# AJH_as3320_HPF_03_4hp.net
KiCad netlist of a schematic drawn in EAGLE
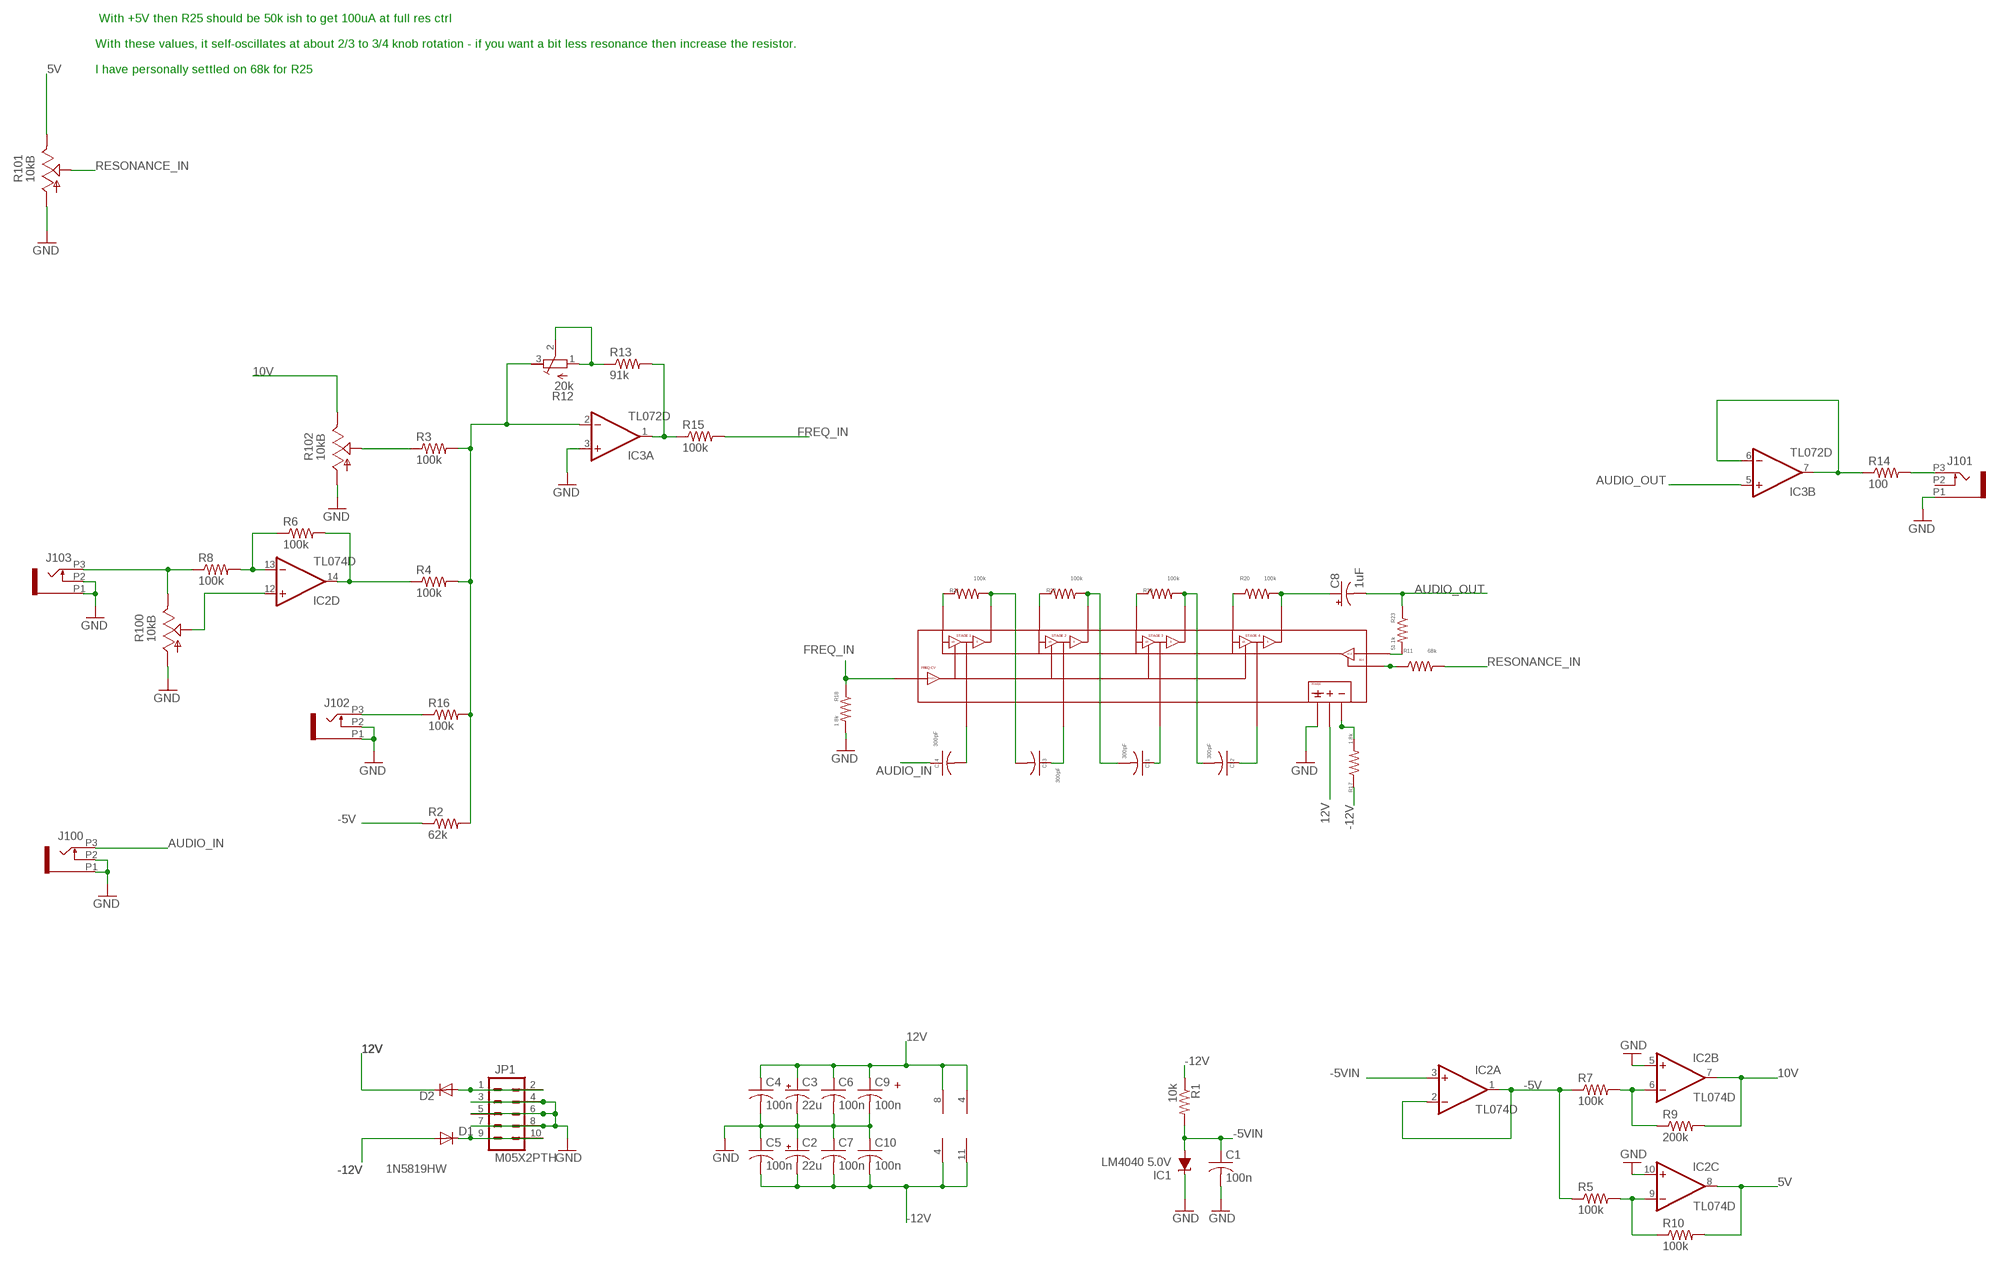
[diagram p0: schematic, sheet 1]

(export (version "E")
  (design (tool "Eeschema 10.0.6"))
  (components
    (comp (ref "C1")
      (value "100n")
      (footprint "eagle-import:C0603")
      (libsource (lib "eagle-import") (part "C-USC0603"))
    )
    (comp (ref "C2")
      (value "22u")
      (footprint "eagle-import:PANASONIC_B")
      (libsource (lib "eagle-import") (part "CPOL-USB"))
    )
    (comp (ref "C3")
      (value "22u")
      (footprint "eagle-import:PANASONIC_B")
      (libsource (lib "eagle-import") (part "CPOL-USB"))
    )
    (comp (ref "C4")
      (value "100n")
      (footprint "eagle-import:C0603")
      (libsource (lib "eagle-import") (part "C-USC0603"))
    )
    (comp (ref "C5")
      (value "100n")
      (footprint "eagle-import:C0603")
      (libsource (lib "eagle-import") (part "C-USC0603"))
    )
    (comp (ref "C6")
      (value "100n")
      (footprint "eagle-import:C0603")
      (libsource (lib "eagle-import") (part "C-USC0603"))
    )
    (comp (ref "C7")
      (value "100n")
      (footprint "eagle-import:C0603")
      (libsource (lib "eagle-import") (part "C-USC0603"))
    )
    (comp (ref "C8")
      (value "1uF")
      (footprint "eagle-import:PANASONIC_B")
      (libsource (lib "eagle-import") (part "rcl_334_CPOL-USB"))
    )
    (comp (ref "C9")
      (value "100n")
      (footprint "eagle-import:C0603")
      (libsource (lib "eagle-import") (part "C-USC0603"))
    )
    (comp (ref "C10")
      (value "100n")
      (footprint "eagle-import:C0603")
      (libsource (lib "eagle-import") (part "C-USC0603"))
    )
    (comp (ref "C11")
      (value "300pF")
      (footprint "eagle-import:C0603")
      (libsource (lib "eagle-import") (part "rcl_334_C-USC0603"))
    )
    (comp (ref "C12")
      (value "300pF")
      (footprint "eagle-import:C0603")
      (libsource (lib "eagle-import") (part "rcl_334_C-USC0603"))
    )
    (comp (ref "C13")
      (value "300pF")
      (footprint "eagle-import:C0603")
      (libsource (lib "eagle-import") (part "rcl_334_C-USC0603"))
    )
    (comp (ref "C14")
      (value "300pF")
      (footprint "eagle-import:C0603")
      (libsource (lib "eagle-import") (part "rcl_334_C-USC0603"))
    )
    (comp (ref "D1")
      (value "1N5819HW")
      (footprint "eagle-import:SOD123")
      (libsource (lib "eagle-import") (part "DIODE-SOD123"))
    )
    (comp (ref "D2")
      (value "1N5819HW")
      (footprint "eagle-import:SOD123")
      (libsource (lib "eagle-import") (part "DIODE-SOD123"))
    )
    (comp (ref "IC1")
      (value "LM4040 5.0V")
      (footprint "eagle-import:DBZ_R-PDSO-G3")
      (libsource (lib "eagle-import") (part "LM4041DBZC12"))
    )
    (comp (ref "IC2")
      (value "TL074D")
      (footprint "eagle-import:SO14")
      (libsource (lib "eagle-import") (part "TL074D"))
    )
    (comp (ref "IC3")
      (value "TL072D")
      (footprint "eagle-import:SO08")
      (libsource (lib "eagle-import") (part "TL072D"))
    )
    (comp (ref "IC4")
      (value "CEM3320_UNFOLDEDQFN")
      (footprint "eagle-import:QFN24")
      (libsource (lib "eagle-import") (part "CEM3320_UNFOLDEDQFN"))
    )
    (comp (ref "J100")
      (value "PJ301_THONKICONN6")
      (footprint "eagle-import:WQP_PJ_301M6")
      (libsource (lib "eagle-import") (part "PJ301_THONKICONN6"))
    )
    (comp (ref "J101")
      (value "PJ301_THONKICONN6")
      (footprint "eagle-import:WQP_PJ_301M6")
      (libsource (lib "eagle-import") (part "PJ301_THONKICONN6"))
    )
    (comp (ref "J102")
      (value "PJ301_THONKICONN6")
      (footprint "eagle-import:WQP_PJ_301M6")
      (libsource (lib "eagle-import") (part "PJ301_THONKICONN6"))
    )
    (comp (ref "J103")
      (value "PJ301_THONKICONN6")
      (footprint "eagle-import:WQP_PJ_301M6")
      (libsource (lib "eagle-import") (part "PJ301_THONKICONN6"))
    )
    (comp (ref "JP1")
      (value "M05X2PTH")
      (footprint "eagle-import:AVR_ICSP")
      (libsource (lib "eagle-import") (part "M05X2PTH"))
    )
    (comp (ref "R1")
      (value "10k")
      (footprint "eagle-import:R0603")
      (libsource (lib "eagle-import") (part "resistor_R-US_R0603"))
    )
    (comp (ref "R2")
      (value "62k")
      (footprint "eagle-import:R0603")
      (libsource (lib "eagle-import") (part "resistor_R-US_R0603"))
    )
    (comp (ref "R3")
      (value "100k")
      (footprint "eagle-import:R0603")
      (libsource (lib "eagle-import") (part "resistor_R-US_R0603"))
    )
    (comp (ref "R4")
      (value "100k")
      (footprint "eagle-import:R0603")
      (libsource (lib "eagle-import") (part "resistor_R-US_R0603"))
    )
    (comp (ref "R5")
      (value "100k")
      (footprint "eagle-import:R0603")
      (libsource (lib "eagle-import") (part "resistor_R-US_R0603"))
    )
    (comp (ref "R6")
      (value "100k")
      (footprint "eagle-import:R0603")
      (libsource (lib "eagle-import") (part "resistor_R-US_R0603"))
    )
    (comp (ref "R7")
      (value "100k")
      (footprint "eagle-import:R0603")
      (libsource (lib "eagle-import") (part "resistor_R-US_R0603"))
    )
    (comp (ref "R8")
      (value "100k")
      (footprint "eagle-import:R0603")
      (libsource (lib "eagle-import") (part "resistor_R-US_R0603"))
    )
    (comp (ref "R9")
      (value "200k")
      (footprint "eagle-import:R0603")
      (libsource (lib "eagle-import") (part "resistor_R-US_R0603"))
    )
    (comp (ref "R10")
      (value "100k")
      (footprint "eagle-import:R0603")
      (libsource (lib "eagle-import") (part "resistor_R-US_R0603"))
    )
    (comp (ref "R11")
      (value "68k")
      (footprint "eagle-import:R0603")
      (libsource (lib "eagle-import") (part "R-US_R0603"))
    )
    (comp (ref "R12")
      (value "20k")
      (footprint "eagle-import:RTRIM3296X")
      (libsource (lib "eagle-import") (part "R-TRIMM3296X"))
    )
    (comp (ref "R13")
      (value "91k")
      (footprint "eagle-import:R0603")
      (libsource (lib "eagle-import") (part "resistor_R-US_R0603"))
    )
    (comp (ref "R14")
      (value "100")
      (footprint "eagle-import:R0603")
      (libsource (lib "eagle-import") (part "resistor_R-US_R0603"))
    )
    (comp (ref "R15")
      (value "100k")
      (footprint "eagle-import:R0603")
      (libsource (lib "eagle-import") (part "resistor_R-US_R0603"))
    )
    (comp (ref "R16")
      (value "100k")
      (footprint "eagle-import:R0603")
      (libsource (lib "eagle-import") (part "resistor_R-US_R0603"))
    )
    (comp (ref "R17")
      (value "1.8k")
      (footprint "eagle-import:R0603")
      (libsource (lib "eagle-import") (part "R-US_R0603"))
    )
    (comp (ref "R18")
      (value "1.8k")
      (footprint "eagle-import:R0603")
      (libsource (lib "eagle-import") (part "R-US_R0603"))
    )
    (comp (ref "R19")
      (value "100k")
      (footprint "eagle-import:R0603")
      (libsource (lib "eagle-import") (part "resistor_348_R-US_R0603"))
    )
    (comp (ref "R20")
      (value "100k")
      (footprint "eagle-import:R0603")
      (libsource (lib "eagle-import") (part "resistor_348_R-US_R0603"))
    )
    (comp (ref "R21")
      (value "100k")
      (footprint "eagle-import:R0603")
      (libsource (lib "eagle-import") (part "resistor_348_R-US_R0603"))
    )
    (comp (ref "R22")
      (value "100k")
      (footprint "eagle-import:R0603")
      (libsource (lib "eagle-import") (part "resistor_348_R-US_R0603"))
    )
    (comp (ref "R23")
      (value "51.1k")
      (footprint "eagle-import:R0603")
      (libsource (lib "eagle-import") (part "R-US_R0603"))
    )
    (comp (ref "R100")
      (value "10kB")
      (footprint "eagle-import:ALPS_POT_VERTICAL")
      (libsource (lib "eagle-import") (part "POT_USVERTICAL"))
    )
    (comp (ref "R101")
      (value "10kB")
      (footprint "eagle-import:ALPS_POT_VERTICAL")
      (libsource (lib "eagle-import") (part "POT_USVERTICAL"))
    )
    (comp (ref "R102")
      (value "10kB")
      (footprint "eagle-import:ALPS_POT_VERTICAL")
      (libsource (lib "eagle-import") (part "POT_USVERTICAL"))
    )
  )
  (nets
    (net (code "1") (name "/-5V") (class "Default")
      (node (ref "IC2") (pin "1") (pinfunction "OUT_1") (pintype "output"))
      (node (ref "IC2") (pin "2") (pinfunction "-IN_2") (pintype "input"))
      (node (ref "R2") (pin "1") (pinfunction "1_1") (pintype "passive"))
      (node (ref "R5") (pin "1") (pinfunction "1_1") (pintype "passive"))
      (node (ref "R7") (pin "1") (pinfunction "1_1") (pintype "passive"))
    )
    (net (code "2") (name "/-5VIN") (class "Default")
      (node (ref "C1") (pin "1") (pinfunction "1_1") (pintype "passive"))
      (node (ref "IC1") (pin "2") (pinfunction "A_2") (pintype "passive"))
      (node (ref "IC2") (pin "3") (pinfunction "+IN_3") (pintype "input"))
      (node (ref "R1") (pin "2") (pinfunction "2_2") (pintype "passive"))
    )
    (net (code "3") (name "/-12V") (class "Default")
      (node (ref "C10") (pin "2") (pinfunction "2_2") (pintype "passive"))
      (node (ref "C2") (pin "-") (pinfunction "-_-") (pintype "passive"))
      (node (ref "C5") (pin "2") (pinfunction "2_2") (pintype "passive"))
      (node (ref "C7") (pin "2") (pinfunction "2_2") (pintype "passive"))
      (node (ref "D1") (pin "A") (pinfunction "A_A") (pintype "passive"))
      (node (ref "IC2") (pin "11") (pinfunction "V-_11") (pintype "power_in"))
      (node (ref "IC3") (pin "4") (pinfunction "V-_4") (pintype "power_in"))
      (node (ref "R1") (pin "1") (pinfunction "1_1") (pintype "passive"))
      (node (ref "R17") (pin "1") (pinfunction "1_1") (pintype "passive"))
    )
    (net (code "4") (name "/5V") (class "Default")
      (node (ref "IC2") (pin "8") (pinfunction "OUT_8") (pintype "output"))
      (node (ref "R10") (pin "2") (pinfunction "2_2") (pintype "passive"))
      (node (ref "R101") (pin "P$1") (pinfunction "E_P$1") (pintype "passive"))
    )
    (net (code "5") (name "/10V") (class "Default")
      (node (ref "IC2") (pin "7") (pinfunction "OUT_7") (pintype "output"))
      (node (ref "R102") (pin "P$1") (pinfunction "E_P$1") (pintype "passive"))
      (node (ref "R9") (pin "2") (pinfunction "2_2") (pintype "passive"))
    )
    (net (code "6") (name "/12V") (class "Default")
      (node (ref "C3") (pin "+") (pinfunction "+_+") (pintype "passive"))
      (node (ref "C4") (pin "1") (pinfunction "1_1") (pintype "passive"))
      (node (ref "C6") (pin "1") (pinfunction "1_1") (pintype "passive"))
      (node (ref "C9") (pin "1") (pinfunction "1_1") (pintype "passive"))
      (node (ref "D2") (pin "C") (pinfunction "C_C") (pintype "passive"))
      (node (ref "IC2") (pin "4") (pinfunction "V+_4") (pintype "power_in"))
      (node (ref "IC3") (pin "8") (pinfunction "V+_8") (pintype "power_in"))
      (node (ref "IC4") (pin "P$22") (pinfunction "POSRAIL_P$22") (pintype "bidirectional"))
    )
    (net (code "7") (name "/AUDIO_IN") (class "Default")
      (node (ref "C14") (pin "1") (pinfunction "1_1") (pintype "passive"))
      (node (ref "J100") (pin "P3") (pinfunction "3_P3") (pintype "passive"))
    )
    (net (code "8") (name "/AUDIO_OUT") (class "Default")
      (node (ref "C8") (pin "-") (pinfunction "-_-") (pintype "passive"))
      (node (ref "IC3") (pin "5") (pinfunction "+IN_5") (pintype "input"))
      (node (ref "R23") (pin "1") (pinfunction "1_1") (pintype "passive"))
    )
    (net (code "9") (name "/FREQ_IN") (class "Default")
      (node (ref "IC4") (pin "P$19") (pinfunction "FREQCV_P$19") (pintype "bidirectional"))
      (node (ref "R15") (pin "2") (pinfunction "2_2") (pintype "passive"))
      (node (ref "R18") (pin "1") (pinfunction "1_1") (pintype "passive"))
    )
    (net (code "10") (name "/RESONANCE_IN") (class "Default")
      (node (ref "R101") (pin "P$2") (pinfunction "S_P$2") (pintype "passive"))
      (node (ref "R11") (pin "2") (pinfunction "2_2") (pintype "passive"))
    )
    (net (code "11") (name "GND") (class "Default")
      (node (ref "C1") (pin "2") (pinfunction "2_2") (pintype "passive"))
      (node (ref "C10") (pin "1") (pinfunction "1_1") (pintype "passive"))
      (node (ref "C2") (pin "+") (pinfunction "+_+") (pintype "passive"))
      (node (ref "C3") (pin "-") (pinfunction "-_-") (pintype "passive"))
      (node (ref "C4") (pin "2") (pinfunction "2_2") (pintype "passive"))
      (node (ref "C5") (pin "1") (pinfunction "1_1") (pintype "passive"))
      (node (ref "C6") (pin "2") (pinfunction "2_2") (pintype "passive"))
      (node (ref "C7") (pin "1") (pinfunction "1_1") (pintype "passive"))
      (node (ref "C9") (pin "2") (pinfunction "2_2") (pintype "passive"))
      (node (ref "IC1") (pin "1") (pinfunction "C_1") (pintype "passive"))
      (node (ref "IC2") (pin "10") (pinfunction "+IN_10") (pintype "input"))
      (node (ref "IC2") (pin "5") (pinfunction "+IN_5") (pintype "input"))
      (node (ref "IC3") (pin "3") (pinfunction "+IN_3") (pintype "input"))
      (node (ref "IC4") (pin "P$7") (pinfunction "GROUND_P$7") (pintype "bidirectional"))
      (node (ref "J100") (pin "P1") (pinfunction "1_P1") (pintype "passive"))
      (node (ref "J100") (pin "P2") (pinfunction "2_P2") (pintype "passive"))
      (node (ref "J101") (pin "P1") (pinfunction "1_P1") (pintype "passive"))
      (node (ref "J102") (pin "P1") (pinfunction "1_P1") (pintype "passive"))
      (node (ref "J102") (pin "P2") (pinfunction "2_P2") (pintype "passive"))
      (node (ref "J103") (pin "P1") (pinfunction "1_P1") (pintype "passive"))
      (node (ref "J103") (pin "P2") (pinfunction "2_P2") (pintype "passive"))
      (node (ref "JP1") (pin "3") (pinfunction "3_3") (pintype "passive"))
      (node (ref "JP1") (pin "4") (pinfunction "4_4") (pintype "passive"))
      (node (ref "JP1") (pin "5") (pinfunction "5_5") (pintype "passive"))
      (node (ref "JP1") (pin "6") (pinfunction "6_6") (pintype "passive"))
      (node (ref "JP1") (pin "7") (pinfunction "7_7") (pintype "passive"))
      (node (ref "JP1") (pin "8") (pinfunction "8_8") (pintype "passive"))
      (node (ref "R100") (pin "P$3") (pinfunction "A_P$3") (pintype "passive"))
      (node (ref "R101") (pin "P$3") (pinfunction "A_P$3") (pintype "passive"))
      (node (ref "R102") (pin "P$3") (pinfunction "A_P$3") (pintype "passive"))
      (node (ref "R18") (pin "2") (pinfunction "2_2") (pintype "passive"))
    )
    (net (code "12") (name "Net-(D1-PadC)") (class "Default")
      (node (ref "D1") (pin "C") (pinfunction "C_C") (pintype "passive"))
      (node (ref "JP1") (pin "10") (pinfunction "10_10") (pintype "passive"))
      (node (ref "JP1") (pin "9") (pinfunction "9_9") (pintype "passive"))
    )
    (net (code "13") (name "Net-(D2-PadA)") (class "Default")
      (node (ref "D2") (pin "A") (pinfunction "A_A") (pintype "passive"))
      (node (ref "JP1") (pin "1") (pinfunction "1_1") (pintype "passive"))
      (node (ref "JP1") (pin "2") (pinfunction "2_2") (pintype "passive"))
    )
    (net (code "14") (name "Net-(IC2B--IN)") (class "Default")
      (node (ref "IC2") (pin "6") (pinfunction "-IN_6") (pintype "input"))
      (node (ref "R7") (pin "2") (pinfunction "2_2") (pintype "passive"))
      (node (ref "R9") (pin "1") (pinfunction "1_1") (pintype "passive"))
    )
    (net (code "15") (name "Net-(IC2C--IN)") (class "Default")
      (node (ref "IC2") (pin "9") (pinfunction "-IN_9") (pintype "input"))
      (node (ref "R10") (pin "1") (pinfunction "1_1") (pintype "passive"))
      (node (ref "R5") (pin "2") (pinfunction "2_2") (pintype "passive"))
    )
    (net (code "16") (name "Net-(IC2D-+IN)") (class "Default")
      (node (ref "IC2") (pin "12") (pinfunction "+IN_12") (pintype "input"))
      (node (ref "R100") (pin "P$2") (pinfunction "S_P$2") (pintype "passive"))
    )
    (net (code "17") (name "Net-(IC2D--IN)") (class "Default")
      (node (ref "IC2") (pin "13") (pinfunction "-IN_13") (pintype "input"))
      (node (ref "R6") (pin "1") (pinfunction "1_1") (pintype "passive"))
      (node (ref "R8") (pin "2") (pinfunction "2_2") (pintype "passive"))
    )
    (net (code "18") (name "Net-(IC2D-OUT)") (class "Default")
      (node (ref "IC2") (pin "14") (pinfunction "OUT_14") (pintype "output"))
      (node (ref "R4") (pin "1") (pinfunction "1_1") (pintype "passive"))
      (node (ref "R6") (pin "2") (pinfunction "2_2") (pintype "passive"))
    )
    (net (code "19") (name "Net-(IC3A--IN)") (class "Default")
      (node (ref "IC3") (pin "2") (pinfunction "-IN_2") (pintype "input"))
      (node (ref "R12") (pin "3") (pinfunction "A_3") (pintype "passive"))
      (node (ref "R16") (pin "2") (pinfunction "2_2") (pintype "passive"))
      (node (ref "R2") (pin "2") (pinfunction "2_2") (pintype "passive"))
      (node (ref "R3") (pin "2") (pinfunction "2_2") (pintype "passive"))
      (node (ref "R4") (pin "2") (pinfunction "2_2") (pintype "passive"))
    )
    (net (code "20") (name "Net-(IC3A-OUT)") (class "Default")
      (node (ref "IC3") (pin "1") (pinfunction "OUT_1") (pintype "output"))
      (node (ref "R13") (pin "2") (pinfunction "2_2") (pintype "passive"))
      (node (ref "R15") (pin "1") (pinfunction "1_1") (pintype "passive"))
    )
    (net (code "21") (name "Net-(IC3B--IN)") (class "Default")
      (node (ref "IC3") (pin "6") (pinfunction "-IN_6") (pintype "input"))
      (node (ref "IC3") (pin "7") (pinfunction "OUT_7") (pintype "output"))
      (node (ref "R14") (pin "1") (pinfunction "1_1") (pintype "passive"))
    )
    (net (code "22") (name "Net-(IC4-FEEDBACK_IN)") (class "Default")
      (node (ref "IC4") (pin "P$14") (pinfunction "FEEDBACK_IN_P$14") (pintype "bidirectional"))
      (node (ref "R23") (pin "2") (pinfunction "2_2") (pintype "passive"))
    )
    (net (code "23") (name "Net-(IC4-NEGRAIL)") (class "Default")
      (node (ref "IC4") (pin "P$20") (pinfunction "NEGRAIL_P$20") (pintype "bidirectional"))
      (node (ref "R17") (pin "2") (pinfunction "2_2") (pintype "passive"))
    )
    (net (code "24") (name "Net-(IC4-RESONANCE_CV)") (class "Default")
      (node (ref "IC4") (pin "P$15") (pinfunction "RESONANCE_CV_P$15") (pintype "bidirectional"))
      (node (ref "R11") (pin "1") (pinfunction "1_1") (pintype "passive"))
    )
    (net (code "25") (name "Net-(IC4-STAGE1_CAP)") (class "Default")
      (node (ref "C14") (pin "2") (pinfunction "2_2") (pintype "passive"))
      (node (ref "IC4") (pin "P$9") (pinfunction "STAGE1_CAP_P$9") (pintype "bidirectional"))
    )
    (net (code "26") (name "Net-(IC4-STAGE1_IN)") (class "Default")
      (node (ref "IC4") (pin "P$4") (pinfunction "STAGE1_IN_P$4") (pintype "bidirectional"))
      (node (ref "R21") (pin "1") (pinfunction "1_1") (pintype "passive"))
    )
    (net (code "27") (name "Net-(IC4-STAGE1_OUT)") (class "Default")
      (node (ref "C13") (pin "2") (pinfunction "2_2") (pintype "passive"))
      (node (ref "IC4") (pin "P$12") (pinfunction "STAGE1_OUT_P$12") (pintype "bidirectional"))
      (node (ref "R21") (pin "2") (pinfunction "2_2") (pintype "passive"))
    )
    (net (code "28") (name "Net-(IC4-STAGE2_CAP)") (class "Default")
      (node (ref "C13") (pin "1") (pinfunction "1_1") (pintype "passive"))
      (node (ref "IC4") (pin "P$8") (pinfunction "STAGE2_CAP_P$8") (pintype "bidirectional"))
    )
    (net (code "29") (name "Net-(IC4-STAGE2_IN)") (class "Default")
      (node (ref "IC4") (pin "P$5") (pinfunction "STAGE2_IN_P$5") (pintype "bidirectional"))
      (node (ref "R22") (pin "1") (pinfunction "1_1") (pintype "passive"))
    )
    (net (code "30") (name "Net-(IC4-STAGE2_OUT)") (class "Default")
      (node (ref "C11") (pin "2") (pinfunction "2_2") (pintype "passive"))
      (node (ref "IC4") (pin "P$11") (pinfunction "STAGE2_OUT_P$11") (pintype "bidirectional"))
      (node (ref "R22") (pin "2") (pinfunction "2_2") (pintype "passive"))
    )
    (net (code "31") (name "Net-(IC4-STAGE3_CAP)") (class "Default")
      (node (ref "C11") (pin "1") (pinfunction "1_1") (pintype "passive"))
      (node (ref "IC4") (pin "P$24") (pinfunction "STAGE3_CAP_P$24") (pintype "bidirectional"))
    )
    (net (code "32") (name "Net-(IC4-STAGE3_IN)") (class "Default")
      (node (ref "IC4") (pin "P$2") (pinfunction "STAGE3_IN_P$2") (pintype "bidirectional"))
      (node (ref "R19") (pin "1") (pinfunction "1_1") (pintype "passive"))
    )
    (net (code "33") (name "Net-(IC4-STAGE3_OUT)") (class "Default")
      (node (ref "C12") (pin "2") (pinfunction "2_2") (pintype "passive"))
      (node (ref "IC4") (pin "P$23") (pinfunction "STAGE3_OUT_P$23") (pintype "bidirectional"))
      (node (ref "R19") (pin "2") (pinfunction "2_2") (pintype "passive"))
    )
    (net (code "34") (name "Net-(IC4-STAGE4_CAP)") (class "Default")
      (node (ref "C12") (pin "1") (pinfunction "1_1") (pintype "passive"))
      (node (ref "IC4") (pin "P$17") (pinfunction "STAGE4_CAP_P$17") (pintype "bidirectional"))
    )
    (net (code "35") (name "Net-(IC4-STAGE4_IN)") (class "Default")
      (node (ref "IC4") (pin "P$3") (pinfunction "STAGE4_IN_P$3") (pintype "bidirectional"))
      (node (ref "R20") (pin "1") (pinfunction "1_1") (pintype "passive"))
    )
    (net (code "36") (name "Net-(IC4-STAGE4_OUT)") (class "Default")
      (node (ref "C8") (pin "+") (pinfunction "+_+") (pintype "passive"))
      (node (ref "IC4") (pin "P$16") (pinfunction "STAGE4_OUT_P$16") (pintype "bidirectional"))
      (node (ref "R20") (pin "2") (pinfunction "2_2") (pintype "passive"))
    )
    (net (code "37") (name "Net-(J101-3)") (class "Default")
      (node (ref "J101") (pin "P3") (pinfunction "3_P3") (pintype "passive"))
      (node (ref "R14") (pin "2") (pinfunction "2_2") (pintype "passive"))
    )
    (net (code "38") (name "Net-(J102-3)") (class "Default")
      (node (ref "J102") (pin "P3") (pinfunction "3_P3") (pintype "passive"))
      (node (ref "R16") (pin "1") (pinfunction "1_1") (pintype "passive"))
    )
    (net (code "39") (name "Net-(J103-3)") (class "Default")
      (node (ref "J103") (pin "P3") (pinfunction "3_P3") (pintype "passive"))
      (node (ref "R100") (pin "P$1") (pinfunction "E_P$1") (pintype "passive"))
      (node (ref "R8") (pin "1") (pinfunction "1_1") (pintype "passive"))
    )
    (net (code "40") (name "Net-(R12-E)") (class "Default")
      (node (ref "R12") (pin "1") (pinfunction "E_1") (pintype "passive"))
      (node (ref "R12") (pin "2") (pinfunction "S_2") (pintype "passive"))
      (node (ref "R13") (pin "1") (pinfunction "1_1") (pintype "passive"))
    )
    (net (code "41") (name "Net-(R102-S)") (class "Default")
      (node (ref "R102") (pin "P$2") (pinfunction "S_P$2") (pintype "passive"))
      (node (ref "R3") (pin "1") (pinfunction "1_1") (pintype "passive"))
    )
    (net (code "42") (name "unconnected-(J101-2-PadP2)") (class "Default")
      (node (ref "J101") (pin "P2") (pinfunction "2_P2") (pintype "passive"))
    )
  )
)
